# display_device_rev2.net
KiCad netlist of a schematic drawn in EAGLE
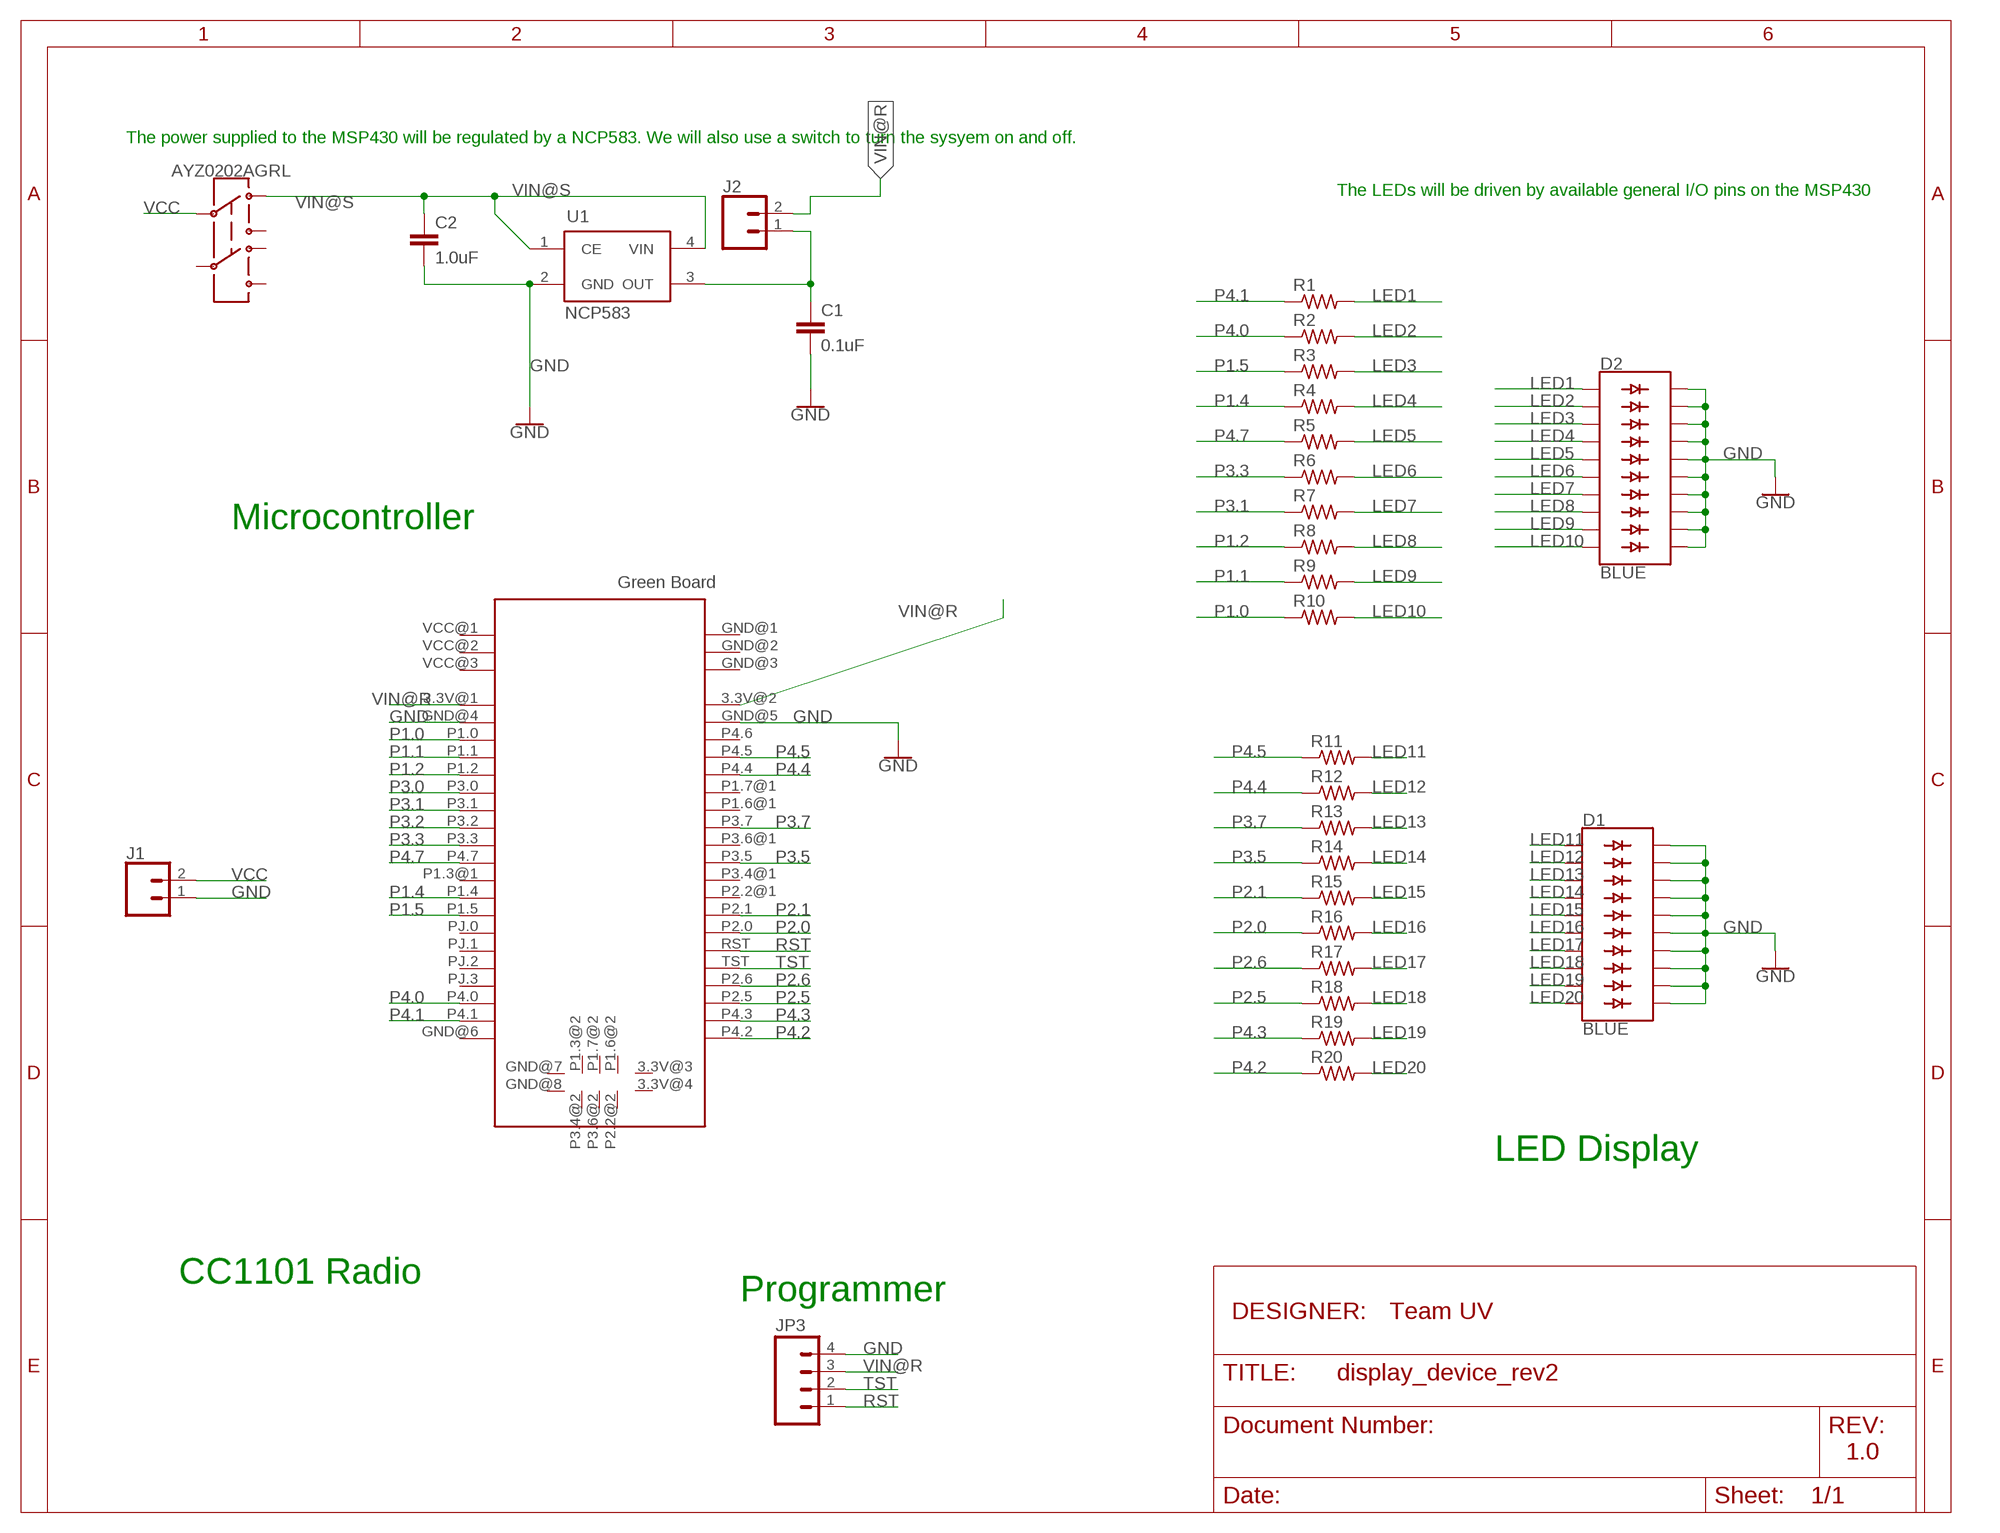
[diagram p0: schematic, sheet 1]

(export (version "E")
  (design (tool "Eeschema 10.0.6"))
  (components
    (comp (ref "AYZ0202AGRL")
      (value "SWITCH-DPDT-SMD-AYZ0202")
      (footprint "eagle-import:SWITCH_DPDT_SMD_AYZ0202")
      (libsource (lib "eagle-import") (part "SWITCH-DPDT-SMD-AYZ0202"))
    )
    (comp (ref "C1")
      (value "0.1uF")
      (footprint "eagle-import:0805")
      (libsource (lib "eagle-import") (part "1.0UF-0805-25V-(+80/-20%)"))
    )
    (comp (ref "C2")
      (value "1.0uF")
      (footprint "eagle-import:0805")
      (libsource (lib "eagle-import") (part "1.0UF-0805-25V-(+80/-20%)"))
    )
    (comp (ref "D1")
      (value "BLUE")
      (footprint "eagle-import:LED_BARGRAPH_10")
      (libsource (lib "eagle-import") (part "LED_BARGRAPH_10BLUE"))
    )
    (comp (ref "D2")
      (value "BLUE")
      (footprint "eagle-import:LED_BARGRAPH_10")
      (libsource (lib "eagle-import") (part "LED_BARGRAPH_10BLUE"))
    )
    (comp (ref "J1")
      (value "CONN_02")
      (footprint "eagle-import:1X02")
      (libsource (lib "eagle-import") (part "CONN_02"))
    )
    (comp (ref "J2")
      (value "CONN_02")
      (footprint "eagle-import:1X02")
      (libsource (lib "eagle-import") (part "CONN_02"))
    )
    (comp (ref "JP3")
      (value "M04PTH")
      (footprint "eagle-import:1X04")
      (libsource (lib "eagle-import") (part "M04PTH"))
    )
    (comp (ref "R1")
      (value "R-US_R0805")
      (footprint "eagle-import:R0805")
      (libsource (lib "eagle-import") (part "R-US_R0805"))
    )
    (comp (ref "R2")
      (value "R-US_R0805")
      (footprint "eagle-import:R0805")
      (libsource (lib "eagle-import") (part "R-US_R0805"))
    )
    (comp (ref "R3")
      (value "R-US_R0805")
      (footprint "eagle-import:R0805")
      (libsource (lib "eagle-import") (part "R-US_R0805"))
    )
    (comp (ref "R4")
      (value "R-US_R0805")
      (footprint "eagle-import:R0805")
      (libsource (lib "eagle-import") (part "R-US_R0805"))
    )
    (comp (ref "R5")
      (value "R-US_R0805")
      (footprint "eagle-import:R0805")
      (libsource (lib "eagle-import") (part "R-US_R0805"))
    )
    (comp (ref "R6")
      (value "R-US_R0805")
      (footprint "eagle-import:R0805")
      (libsource (lib "eagle-import") (part "R-US_R0805"))
    )
    (comp (ref "R7")
      (value "R-US_R0805")
      (footprint "eagle-import:R0805")
      (libsource (lib "eagle-import") (part "R-US_R0805"))
    )
    (comp (ref "R8")
      (value "R-US_R0805")
      (footprint "eagle-import:R0805")
      (libsource (lib "eagle-import") (part "R-US_R0805"))
    )
    (comp (ref "R9")
      (value "R-US_R0805")
      (footprint "eagle-import:R0805")
      (libsource (lib "eagle-import") (part "R-US_R0805"))
    )
    (comp (ref "R10")
      (value "R-US_R0805")
      (footprint "eagle-import:R0805")
      (libsource (lib "eagle-import") (part "R-US_R0805"))
    )
    (comp (ref "R11")
      (value "R-US_R0805")
      (footprint "eagle-import:R0805")
      (libsource (lib "eagle-import") (part "R-US_R0805"))
    )
    (comp (ref "R12")
      (value "R-US_R0805")
      (footprint "eagle-import:R0805")
      (libsource (lib "eagle-import") (part "R-US_R0805"))
    )
    (comp (ref "R13")
      (value "R-US_R0805")
      (footprint "eagle-import:R0805")
      (libsource (lib "eagle-import") (part "R-US_R0805"))
    )
    (comp (ref "R14")
      (value "R-US_R0805")
      (footprint "eagle-import:R0805")
      (libsource (lib "eagle-import") (part "R-US_R0805"))
    )
    (comp (ref "R15")
      (value "R-US_R0805")
      (footprint "eagle-import:R0805")
      (libsource (lib "eagle-import") (part "R-US_R0805"))
    )
    (comp (ref "R16")
      (value "R-US_R0805")
      (footprint "eagle-import:R0805")
      (libsource (lib "eagle-import") (part "R-US_R0805"))
    )
    (comp (ref "R17")
      (value "R-US_R0805")
      (footprint "eagle-import:R0805")
      (libsource (lib "eagle-import") (part "R-US_R0805"))
    )
    (comp (ref "R18")
      (value "R-US_R0805")
      (footprint "eagle-import:R0805")
      (libsource (lib "eagle-import") (part "R-US_R0805"))
    )
    (comp (ref "R19")
      (value "R-US_R0805")
      (footprint "eagle-import:R0805")
      (libsource (lib "eagle-import") (part "R-US_R0805"))
    )
    (comp (ref "R20")
      (value "R-US_R0805")
      (footprint "eagle-import:R0805")
      (libsource (lib "eagle-import") (part "R-US_R0805"))
    )
    (comp (ref "U$1")
      (value "GREEDNBRD")
      (footprint "eagle-import:GREENBRD")
      (libsource (lib "eagle-import") (part "GREEDNBRD"))
    )
    (comp (ref "U1")
      (value "NCP583")
      (footprint "eagle-import:SC82-AB_1PRIMARY")
      (libsource (lib "eagle-import") (part "NCP583"))
    )
  )
  (nets
    (net (code "1") (name "/LED1") (class "Default")
      (node (ref "D2") (pin "1") (pinfunction "A_1") (pintype "passive"))
      (node (ref "R1") (pin "2") (pinfunction "2_2") (pintype "passive"))
    )
    (net (code "2") (name "/LED2") (class "Default")
      (node (ref "D2") (pin "2") (pinfunction "A1_2") (pintype "passive"))
      (node (ref "R2") (pin "2") (pinfunction "2_2") (pintype "passive"))
    )
    (net (code "3") (name "/LED3") (class "Default")
      (node (ref "D2") (pin "3") (pinfunction "A2_3") (pintype "passive"))
      (node (ref "R3") (pin "2") (pinfunction "2_2") (pintype "passive"))
    )
    (net (code "4") (name "/LED4") (class "Default")
      (node (ref "D2") (pin "4") (pinfunction "A3_4") (pintype "passive"))
      (node (ref "R4") (pin "2") (pinfunction "2_2") (pintype "passive"))
    )
    (net (code "5") (name "/LED5") (class "Default")
      (node (ref "D2") (pin "5") (pinfunction "A4_5") (pintype "passive"))
      (node (ref "R5") (pin "2") (pinfunction "2_2") (pintype "passive"))
    )
    (net (code "6") (name "/LED6") (class "Default")
      (node (ref "D2") (pin "6") (pinfunction "A5_6") (pintype "passive"))
      (node (ref "R6") (pin "2") (pinfunction "2_2") (pintype "passive"))
    )
    (net (code "7") (name "/LED7") (class "Default")
      (node (ref "D2") (pin "7") (pinfunction "A6_7") (pintype "passive"))
      (node (ref "R7") (pin "2") (pinfunction "2_2") (pintype "passive"))
    )
    (net (code "8") (name "/LED8") (class "Default")
      (node (ref "D2") (pin "8") (pinfunction "A7_8") (pintype "passive"))
      (node (ref "R8") (pin "2") (pinfunction "2_2") (pintype "passive"))
    )
    (net (code "9") (name "/LED9") (class "Default")
      (node (ref "D2") (pin "9") (pinfunction "A8_9") (pintype "passive"))
      (node (ref "R9") (pin "2") (pinfunction "2_2") (pintype "passive"))
    )
    (net (code "10") (name "/LED10") (class "Default")
      (node (ref "D2") (pin "10") (pinfunction "A9_10") (pintype "passive"))
      (node (ref "R10") (pin "2") (pinfunction "2_2") (pintype "passive"))
    )
    (net (code "11") (name "/LED11") (class "Default")
      (node (ref "D1") (pin "1") (pinfunction "A_1") (pintype "passive"))
      (node (ref "R11") (pin "2") (pinfunction "2_2") (pintype "passive"))
    )
    (net (code "12") (name "/LED12") (class "Default")
      (node (ref "D1") (pin "2") (pinfunction "A1_2") (pintype "passive"))
      (node (ref "R12") (pin "2") (pinfunction "2_2") (pintype "passive"))
    )
    (net (code "13") (name "/LED13") (class "Default")
      (node (ref "D1") (pin "3") (pinfunction "A2_3") (pintype "passive"))
      (node (ref "R13") (pin "2") (pinfunction "2_2") (pintype "passive"))
    )
    (net (code "14") (name "/LED14") (class "Default")
      (node (ref "D1") (pin "4") (pinfunction "A3_4") (pintype "passive"))
      (node (ref "R14") (pin "2") (pinfunction "2_2") (pintype "passive"))
    )
    (net (code "15") (name "/LED15") (class "Default")
      (node (ref "D1") (pin "5") (pinfunction "A4_5") (pintype "passive"))
      (node (ref "R15") (pin "2") (pinfunction "2_2") (pintype "passive"))
    )
    (net (code "16") (name "/LED16") (class "Default")
      (node (ref "D1") (pin "6") (pinfunction "A5_6") (pintype "passive"))
      (node (ref "R16") (pin "2") (pinfunction "2_2") (pintype "passive"))
    )
    (net (code "17") (name "/LED17") (class "Default")
      (node (ref "D1") (pin "7") (pinfunction "A6_7") (pintype "passive"))
      (node (ref "R17") (pin "2") (pinfunction "2_2") (pintype "passive"))
    )
    (net (code "18") (name "/LED18") (class "Default")
      (node (ref "D1") (pin "8") (pinfunction "A7_8") (pintype "passive"))
      (node (ref "R18") (pin "2") (pinfunction "2_2") (pintype "passive"))
    )
    (net (code "19") (name "/LED19") (class "Default")
      (node (ref "D1") (pin "9") (pinfunction "A8_9") (pintype "passive"))
      (node (ref "R19") (pin "2") (pinfunction "2_2") (pintype "passive"))
    )
    (net (code "20") (name "/LED20") (class "Default")
      (node (ref "D1") (pin "10") (pinfunction "A9_10") (pintype "passive"))
      (node (ref "R20") (pin "2") (pinfunction "2_2") (pintype "passive"))
    )
    (net (code "21") (name "/P1.0") (class "Default")
      (node (ref "R10") (pin "1") (pinfunction "1_1") (pintype "passive"))
      (node (ref "U$1") (pin "P1.0") (pinfunction "P1.0_P1.0") (pintype "bidirectional"))
    )
    (net (code "22") (name "/P1.1") (class "Default")
      (node (ref "R9") (pin "1") (pinfunction "1_1") (pintype "passive"))
      (node (ref "U$1") (pin "P1.1") (pinfunction "P1.1_P1.1") (pintype "bidirectional"))
    )
    (net (code "23") (name "/P1.2") (class "Default")
      (node (ref "R8") (pin "1") (pinfunction "1_1") (pintype "passive"))
      (node (ref "U$1") (pin "P1.2") (pinfunction "P1.2_P1.2") (pintype "bidirectional"))
    )
    (net (code "24") (name "/P1.4") (class "Default")
      (node (ref "R4") (pin "1") (pinfunction "1_1") (pintype "passive"))
      (node (ref "U$1") (pin "P1.4") (pinfunction "P1.4_P1.4") (pintype "bidirectional"))
    )
    (net (code "25") (name "/P1.5") (class "Default")
      (node (ref "R3") (pin "1") (pinfunction "1_1") (pintype "passive"))
      (node (ref "U$1") (pin "P1.5") (pinfunction "P1.5_P1.5") (pintype "bidirectional"))
    )
    (net (code "26") (name "/P2.0") (class "Default")
      (node (ref "R16") (pin "1") (pinfunction "1_1") (pintype "passive"))
      (node (ref "U$1") (pin "P2.0") (pinfunction "P2.0_P2.0") (pintype "bidirectional"))
    )
    (net (code "27") (name "/P2.1") (class "Default")
      (node (ref "R15") (pin "1") (pinfunction "1_1") (pintype "passive"))
      (node (ref "U$1") (pin "P2.1") (pinfunction "P2.1_P2.1") (pintype "bidirectional"))
    )
    (net (code "28") (name "/P2.5") (class "Default")
      (node (ref "R18") (pin "1") (pinfunction "1_1") (pintype "passive"))
      (node (ref "U$1") (pin "P2.5") (pinfunction "P2.5_P2.5") (pintype "bidirectional"))
    )
    (net (code "29") (name "/P2.6") (class "Default")
      (node (ref "R17") (pin "1") (pinfunction "1_1") (pintype "passive"))
      (node (ref "U$1") (pin "P2.6") (pinfunction "P2.6_P2.6") (pintype "bidirectional"))
    )
    (net (code "30") (name "/P3.0") (class "Default")
      (node (ref "U$1") (pin "P3.0") (pinfunction "P3.0_P3.0") (pintype "bidirectional"))
    )
    (net (code "31") (name "/P3.1") (class "Default")
      (node (ref "R7") (pin "1") (pinfunction "1_1") (pintype "passive"))
      (node (ref "U$1") (pin "P3.1") (pinfunction "P3.1_P3.1") (pintype "bidirectional"))
    )
    (net (code "32") (name "/P3.2") (class "Default")
      (node (ref "U$1") (pin "P3.2") (pinfunction "P3.2_P3.2") (pintype "bidirectional"))
    )
    (net (code "33") (name "/P3.3") (class "Default")
      (node (ref "R6") (pin "1") (pinfunction "1_1") (pintype "passive"))
      (node (ref "U$1") (pin "P3.3") (pinfunction "P3.3_P3.3") (pintype "bidirectional"))
    )
    (net (code "34") (name "/P3.5") (class "Default")
      (node (ref "R14") (pin "1") (pinfunction "1_1") (pintype "passive"))
      (node (ref "U$1") (pin "P3.5") (pinfunction "P3.5_P3.5") (pintype "bidirectional"))
    )
    (net (code "35") (name "/P3.7") (class "Default")
      (node (ref "R13") (pin "1") (pinfunction "1_1") (pintype "passive"))
      (node (ref "U$1") (pin "P3.7") (pinfunction "P3.7_P3.7") (pintype "bidirectional"))
    )
    (net (code "36") (name "/P4.0") (class "Default")
      (node (ref "R2") (pin "1") (pinfunction "1_1") (pintype "passive"))
      (node (ref "U$1") (pin "P4.0") (pinfunction "P4.0_P4.0") (pintype "bidirectional"))
    )
    (net (code "37") (name "/P4.1") (class "Default")
      (node (ref "R1") (pin "1") (pinfunction "1_1") (pintype "passive"))
      (node (ref "U$1") (pin "P4.1") (pinfunction "P4.1_P4.1") (pintype "bidirectional"))
    )
    (net (code "38") (name "/P4.2") (class "Default")
      (node (ref "R20") (pin "1") (pinfunction "1_1") (pintype "passive"))
      (node (ref "U$1") (pin "P4.2") (pinfunction "P4.2_P4.2") (pintype "bidirectional"))
    )
    (net (code "39") (name "/P4.3") (class "Default")
      (node (ref "R19") (pin "1") (pinfunction "1_1") (pintype "passive"))
      (node (ref "U$1") (pin "P4.3") (pinfunction "P4.3_P4.3") (pintype "bidirectional"))
    )
    (net (code "40") (name "/P4.4") (class "Default")
      (node (ref "R12") (pin "1") (pinfunction "1_1") (pintype "passive"))
      (node (ref "U$1") (pin "P4.4") (pinfunction "P4.4_P4.4") (pintype "bidirectional"))
    )
    (net (code "41") (name "/P4.5") (class "Default")
      (node (ref "R11") (pin "1") (pinfunction "1_1") (pintype "passive"))
      (node (ref "U$1") (pin "P4.5") (pinfunction "P4.5_P4.5") (pintype "bidirectional"))
    )
    (net (code "42") (name "/P4.7") (class "Default")
      (node (ref "R5") (pin "1") (pinfunction "1_1") (pintype "passive"))
      (node (ref "U$1") (pin "P4.7") (pinfunction "P4.7_P4.7") (pintype "bidirectional"))
    )
    (net (code "43") (name "/RST") (class "Default")
      (node (ref "JP3") (pin "1") (pinfunction "1_1") (pintype "passive"))
      (node (ref "U$1") (pin "RST") (pinfunction "RST_RST") (pintype "bidirectional"))
    )
    (net (code "44") (name "/TST") (class "Default")
      (node (ref "JP3") (pin "2") (pinfunction "2_2") (pintype "passive"))
      (node (ref "U$1") (pin "TST") (pinfunction "TST_TST") (pintype "bidirectional"))
    )
    (net (code "45") (name "/VCC") (class "Default")
      (node (ref "AYZ0202AGRL") (pin "2") (pinfunction "2_2") (pintype "bidirectional"))
      (node (ref "J1") (pin "2") (pinfunction "2_2") (pintype "passive"))
    )
    (net (code "46") (name "/VIN@S") (class "Default")
      (node (ref "AYZ0202AGRL") (pin "1") (pinfunction "1_1") (pintype "bidirectional"))
      (node (ref "C2") (pin "1") (pinfunction "1_1") (pintype "passive"))
      (node (ref "U1") (pin "1") (pinfunction "CE_1") (pintype "bidirectional"))
      (node (ref "U1") (pin "4") (pinfunction "VIN_4") (pintype "bidirectional"))
    )
    (net (code "47") (name "GND") (class "Default")
      (node (ref "C1") (pin "2") (pinfunction "2_2") (pintype "passive"))
      (node (ref "C2") (pin "2") (pinfunction "2_2") (pintype "passive"))
      (node (ref "D1") (pin "11") (pinfunction "C9_11") (pintype "passive"))
      (node (ref "D1") (pin "12") (pinfunction "C8_12") (pintype "passive"))
      (node (ref "D1") (pin "13") (pinfunction "C7_13") (pintype "passive"))
      (node (ref "D1") (pin "14") (pinfunction "C6_14") (pintype "passive"))
      (node (ref "D1") (pin "15") (pinfunction "C5_15") (pintype "passive"))
      (node (ref "D1") (pin "16") (pinfunction "C4_16") (pintype "passive"))
      (node (ref "D1") (pin "17") (pinfunction "C3_17") (pintype "passive"))
      (node (ref "D1") (pin "18") (pinfunction "C2_18") (pintype "passive"))
      (node (ref "D1") (pin "19") (pinfunction "C1_19") (pintype "passive"))
      (node (ref "D1") (pin "20") (pinfunction "C_20") (pintype "passive"))
      (node (ref "D2") (pin "11") (pinfunction "C9_11") (pintype "passive"))
      (node (ref "D2") (pin "12") (pinfunction "C8_12") (pintype "passive"))
      (node (ref "D2") (pin "13") (pinfunction "C7_13") (pintype "passive"))
      (node (ref "D2") (pin "14") (pinfunction "C6_14") (pintype "passive"))
      (node (ref "D2") (pin "15") (pinfunction "C5_15") (pintype "passive"))
      (node (ref "D2") (pin "16") (pinfunction "C4_16") (pintype "passive"))
      (node (ref "D2") (pin "17") (pinfunction "C3_17") (pintype "passive"))
      (node (ref "D2") (pin "18") (pinfunction "C2_18") (pintype "passive"))
      (node (ref "D2") (pin "19") (pinfunction "C1_19") (pintype "passive"))
      (node (ref "D2") (pin "20") (pinfunction "C_20") (pintype "passive"))
      (node (ref "J1") (pin "1") (pinfunction "1_1") (pintype "passive"))
      (node (ref "JP3") (pin "4") (pinfunction "4_4") (pintype "passive"))
      (node (ref "U$1") (pin "GND@4") (pinfunction "GND_GND@4") (pintype "bidirectional"))
      (node (ref "U$1") (pin "GND@5") (pinfunction "GND_GND@5") (pintype "bidirectional"))
      (node (ref "U1") (pin "2") (pinfunction "GND_2") (pintype "bidirectional"))
    )
    (net (code "48") (name "Net-(U1-OUT)") (class "Default")
      (node (ref "C1") (pin "1") (pinfunction "1_1") (pintype "passive"))
      (node (ref "J2") (pin "1") (pinfunction "1_1") (pintype "passive"))
      (node (ref "U1") (pin "3") (pinfunction "OUT_3") (pintype "bidirectional"))
    )
    (net (code "49") (name "VIN@R") (class "Default")
      (node (ref "J2") (pin "2") (pinfunction "2_2") (pintype "passive"))
      (node (ref "JP3") (pin "3") (pinfunction "3_3") (pintype "passive"))
      (node (ref "U$1") (pin "3.3V@1") (pinfunction "3.3V_3.3V@1") (pintype "bidirectional"))
      (node (ref "U$1") (pin "3.3V@2") (pinfunction "3.3V_3.3V@2") (pintype "bidirectional"))
    )
    (net (code "50") (name "unconnected-(AYZ0202AGRL-Pad3)") (class "Default")
      (node (ref "AYZ0202AGRL") (pin "3") (pinfunction "3_3") (pintype "bidirectional"))
    )
    (net (code "51") (name "unconnected-(AYZ0202AGRL-Pad4)") (class "Default")
      (node (ref "AYZ0202AGRL") (pin "4") (pinfunction "4_4") (pintype "bidirectional"))
    )
    (net (code "52") (name "unconnected-(AYZ0202AGRL-Pad5)") (class "Default")
      (node (ref "AYZ0202AGRL") (pin "5") (pinfunction "5_5") (pintype "bidirectional"))
    )
    (net (code "53") (name "unconnected-(AYZ0202AGRL-Pad6)") (class "Default")
      (node (ref "AYZ0202AGRL") (pin "6") (pinfunction "6_6") (pintype "bidirectional"))
    )
    (net (code "54") (name "unconnected-(U$1-3.3V-Pad3.3V@3)") (class "Default")
      (node (ref "U$1") (pin "3.3V@3") (pinfunction "3.3V_3.3V@3") (pintype "bidirectional"))
    )
    (net (code "55") (name "unconnected-(U$1-3.3V-Pad3.3V@4)") (class "Default")
      (node (ref "U$1") (pin "3.3V@4") (pinfunction "3.3V_3.3V@4") (pintype "bidirectional"))
    )
    (net (code "56") (name "unconnected-(U$1-GND-PadGND@1)") (class "Default")
      (node (ref "U$1") (pin "GND@1") (pinfunction "GND_GND@1") (pintype "bidirectional"))
    )
    (net (code "57") (name "unconnected-(U$1-GND-PadGND@2)") (class "Default")
      (node (ref "U$1") (pin "GND@2") (pinfunction "GND_GND@2") (pintype "bidirectional"))
    )
    (net (code "58") (name "unconnected-(U$1-GND-PadGND@3)") (class "Default")
      (node (ref "U$1") (pin "GND@3") (pinfunction "GND_GND@3") (pintype "bidirectional"))
    )
    (net (code "59") (name "unconnected-(U$1-GND-PadGND@6)") (class "Default")
      (node (ref "U$1") (pin "GND@6") (pinfunction "GND_GND@6") (pintype "bidirectional"))
    )
    (net (code "60") (name "unconnected-(U$1-GND-PadGND@7)") (class "Default")
      (node (ref "U$1") (pin "GND@7") (pinfunction "GND_GND@7") (pintype "bidirectional"))
    )
    (net (code "61") (name "unconnected-(U$1-GND-PadGND@8)") (class "Default")
      (node (ref "U$1") (pin "GND@8") (pinfunction "GND_GND@8") (pintype "bidirectional"))
    )
    (net (code "62") (name "unconnected-(U$1-P1.3-PadP1.3@1)") (class "Default")
      (node (ref "U$1") (pin "P1.3@1") (pinfunction "P1.3_P1.3@1") (pintype "bidirectional"))
    )
    (net (code "63") (name "unconnected-(U$1-P1.3-PadP1.3@2)") (class "Default")
      (node (ref "U$1") (pin "P1.3@2") (pinfunction "P1.3_P1.3@2") (pintype "bidirectional"))
    )
    (net (code "64") (name "unconnected-(U$1-P1.6-PadP1.6@1)") (class "Default")
      (node (ref "U$1") (pin "P1.6@1") (pinfunction "P1.6_P1.6@1") (pintype "bidirectional"))
    )
    (net (code "65") (name "unconnected-(U$1-P1.6-PadP1.6@2)") (class "Default")
      (node (ref "U$1") (pin "P1.6@2") (pinfunction "P1.6_P1.6@2") (pintype "bidirectional"))
    )
    (net (code "66") (name "unconnected-(U$1-P1.7-PadP1.7@1)") (class "Default")
      (node (ref "U$1") (pin "P1.7@1") (pinfunction "P1.7_P1.7@1") (pintype "bidirectional"))
    )
    (net (code "67") (name "unconnected-(U$1-P1.7-PadP1.7@2)") (class "Default")
      (node (ref "U$1") (pin "P1.7@2") (pinfunction "P1.7_P1.7@2") (pintype "bidirectional"))
    )
    (net (code "68") (name "unconnected-(U$1-P2.2-PadP2.2@1)") (class "Default")
      (node (ref "U$1") (pin "P2.2@1") (pinfunction "P2.2_P2.2@1") (pintype "bidirectional"))
    )
    (net (code "69") (name "unconnected-(U$1-P2.2-PadP2.2@2)") (class "Default")
      (node (ref "U$1") (pin "P2.2@2") (pinfunction "P2.2_P2.2@2") (pintype "bidirectional"))
    )
    (net (code "70") (name "unconnected-(U$1-P3.4-PadP3.4@1)") (class "Default")
      (node (ref "U$1") (pin "P3.4@1") (pinfunction "P3.4_P3.4@1") (pintype "bidirectional"))
    )
    (net (code "71") (name "unconnected-(U$1-P3.4-PadP3.4@2)") (class "Default")
      (node (ref "U$1") (pin "P3.4@2") (pinfunction "P3.4_P3.4@2") (pintype "bidirectional"))
    )
    (net (code "72") (name "unconnected-(U$1-P3.6-PadP3.6@1)") (class "Default")
      (node (ref "U$1") (pin "P3.6@1") (pinfunction "P3.6_P3.6@1") (pintype "bidirectional"))
    )
    (net (code "73") (name "unconnected-(U$1-P3.6-PadP3.6@2)") (class "Default")
      (node (ref "U$1") (pin "P3.6@2") (pinfunction "P3.6_P3.6@2") (pintype "bidirectional"))
    )
    (net (code "74") (name "unconnected-(U$1-PadP4.6)") (class "Default")
      (node (ref "U$1") (pin "P4.6") (pinfunction "P4.6_P4.6") (pintype "bidirectional"))
    )
    (net (code "75") (name "unconnected-(U$1-PadPJ.0)") (class "Default")
      (node (ref "U$1") (pin "PJ.0") (pinfunction "PJ.0_PJ.0") (pintype "bidirectional"))
    )
    (net (code "76") (name "unconnected-(U$1-PadPJ.1)") (class "Default")
      (node (ref "U$1") (pin "PJ.1") (pinfunction "PJ.1_PJ.1") (pintype "bidirectional"))
    )
    (net (code "77") (name "unconnected-(U$1-PadPJ.2)") (class "Default")
      (node (ref "U$1") (pin "PJ.2") (pinfunction "PJ.2_PJ.2") (pintype "bidirectional"))
    )
    (net (code "78") (name "unconnected-(U$1-PadPJ.3)") (class "Default")
      (node (ref "U$1") (pin "PJ.3") (pinfunction "PJ.3_PJ.3") (pintype "bidirectional"))
    )
    (net (code "79") (name "unconnected-(U$1-VCC-PadVCC@1)") (class "Default")
      (node (ref "U$1") (pin "VCC@1") (pinfunction "VCC_VCC@1") (pintype "bidirectional"))
    )
    (net (code "80") (name "unconnected-(U$1-VCC-PadVCC@2)") (class "Default")
      (node (ref "U$1") (pin "VCC@2") (pinfunction "VCC_VCC@2") (pintype "bidirectional"))
    )
    (net (code "81") (name "unconnected-(U$1-VCC-PadVCC@3)") (class "Default")
      (node (ref "U$1") (pin "VCC@3") (pinfunction "VCC_VCC@3") (pintype "bidirectional"))
    )
  )
)
